# PSPS_AVNC_SRD_sensors-2020-09-19.net
KiCad netlist of a schematic drawn in EAGLE
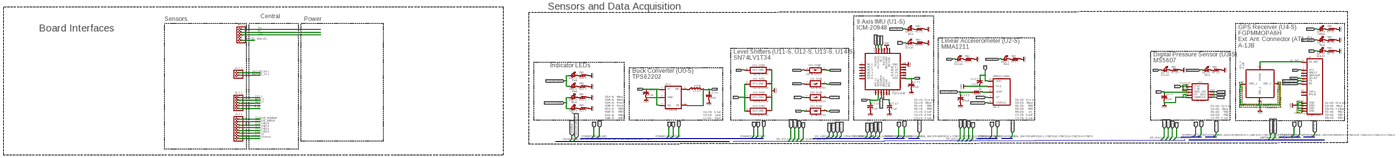
[diagram p0: schematic, sheet 1, overview]
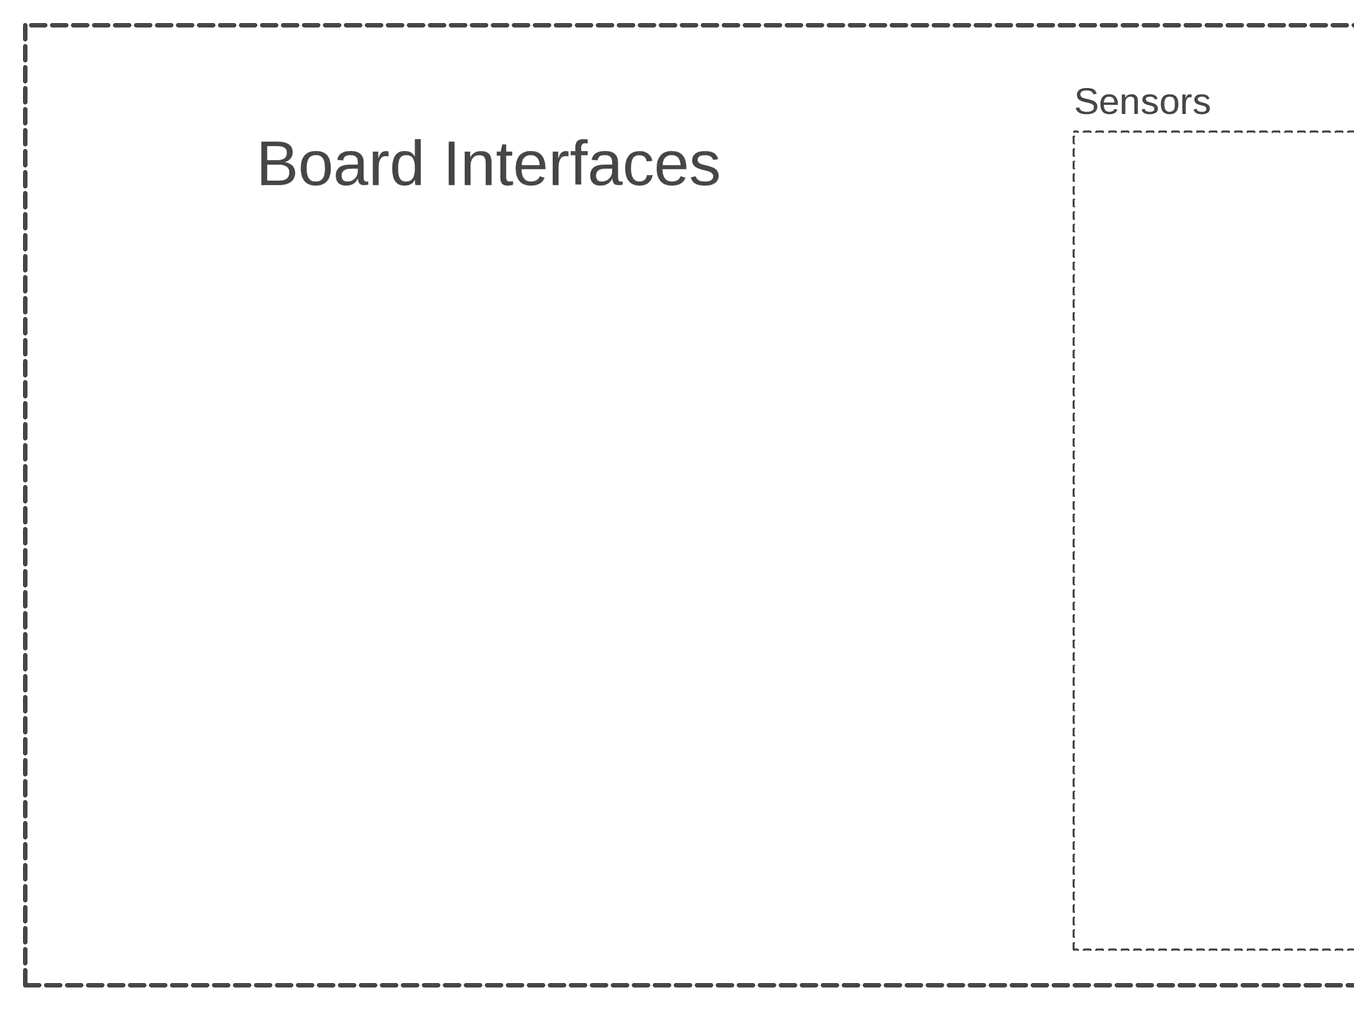
[diagram p1: schematic, sheet 1, part 1 of 4]
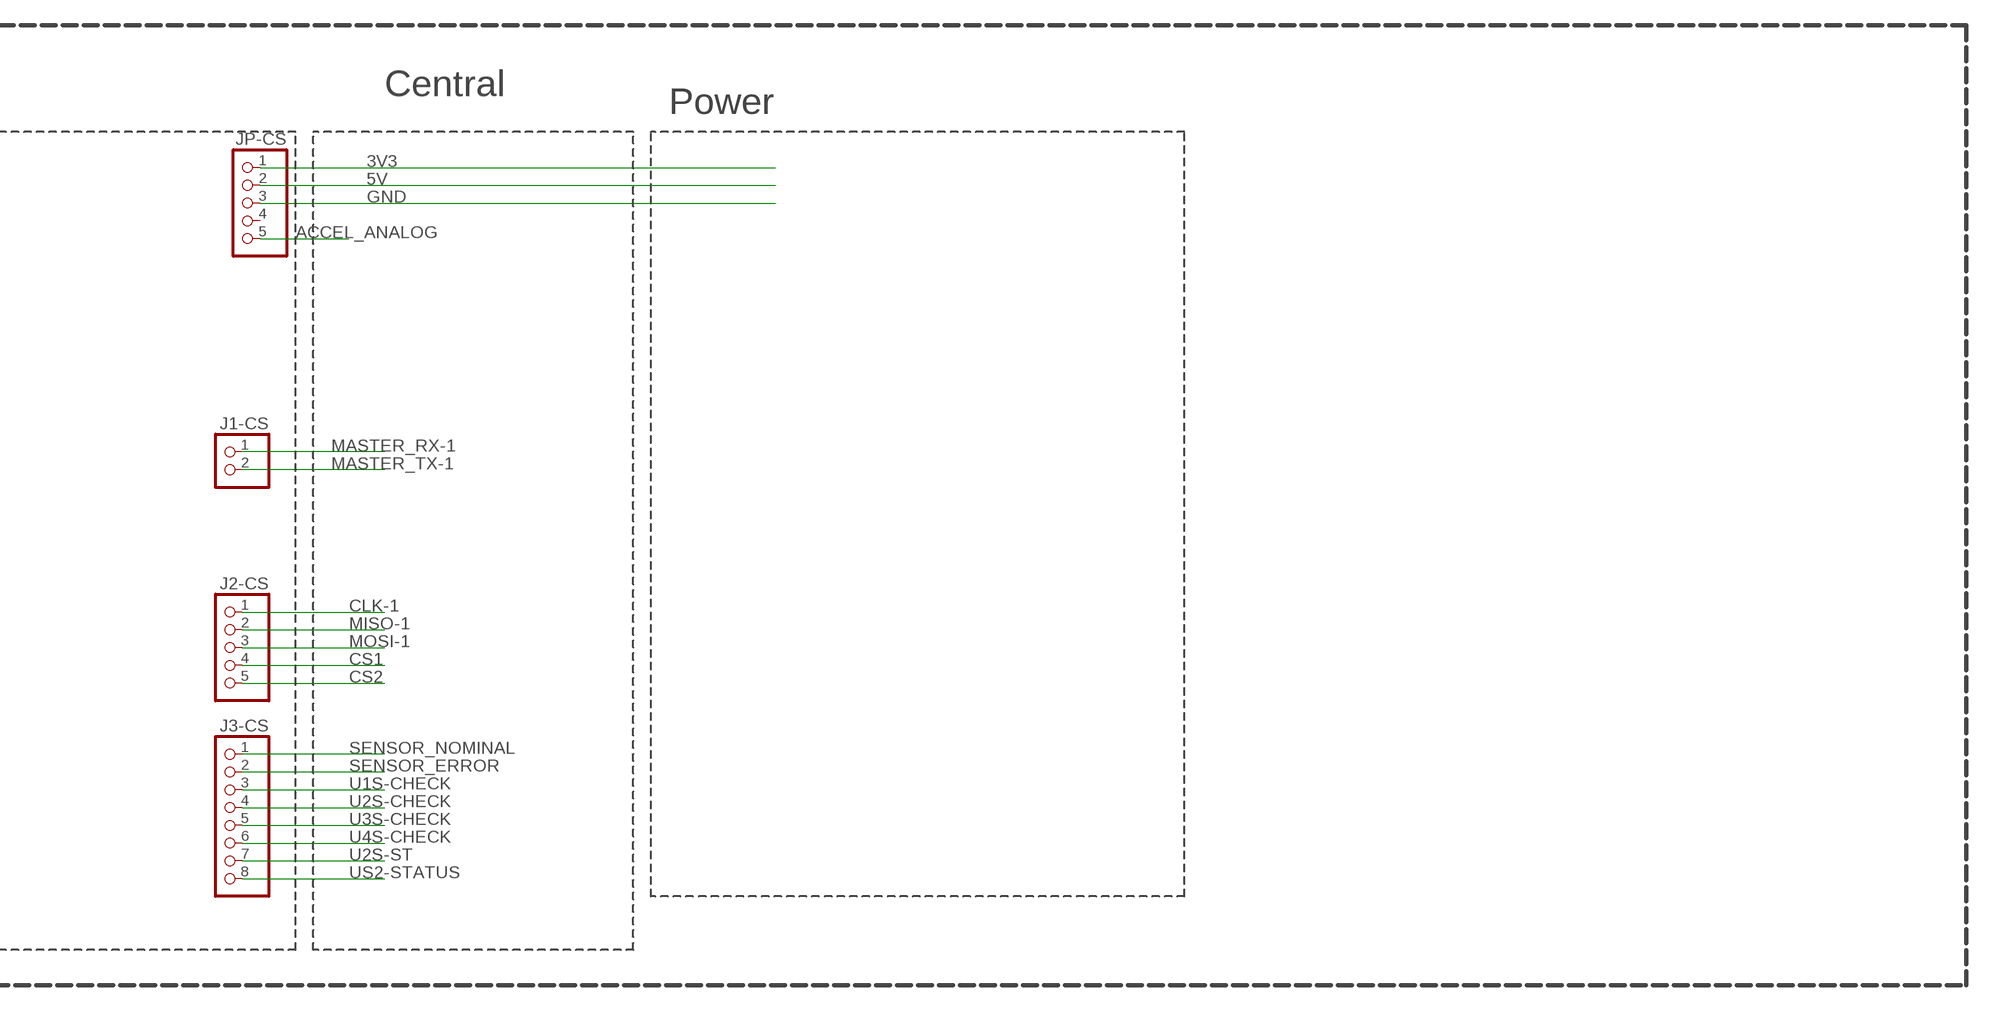
[diagram p2: schematic, sheet 1, part 2 of 4]
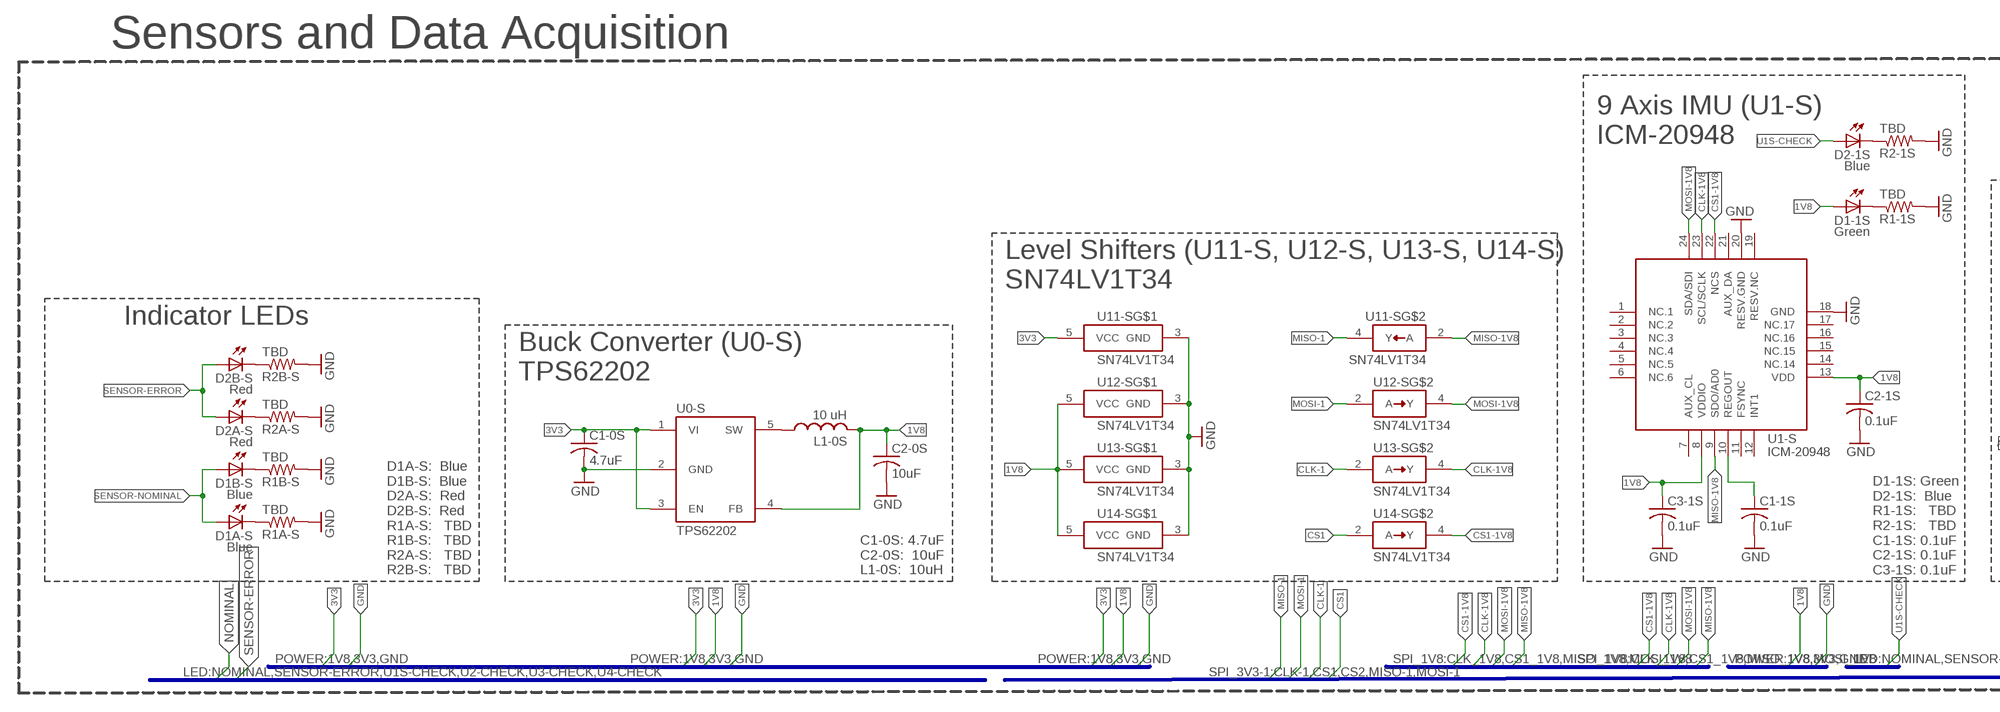
[diagram p3: schematic, sheet 1, part 3 of 4]
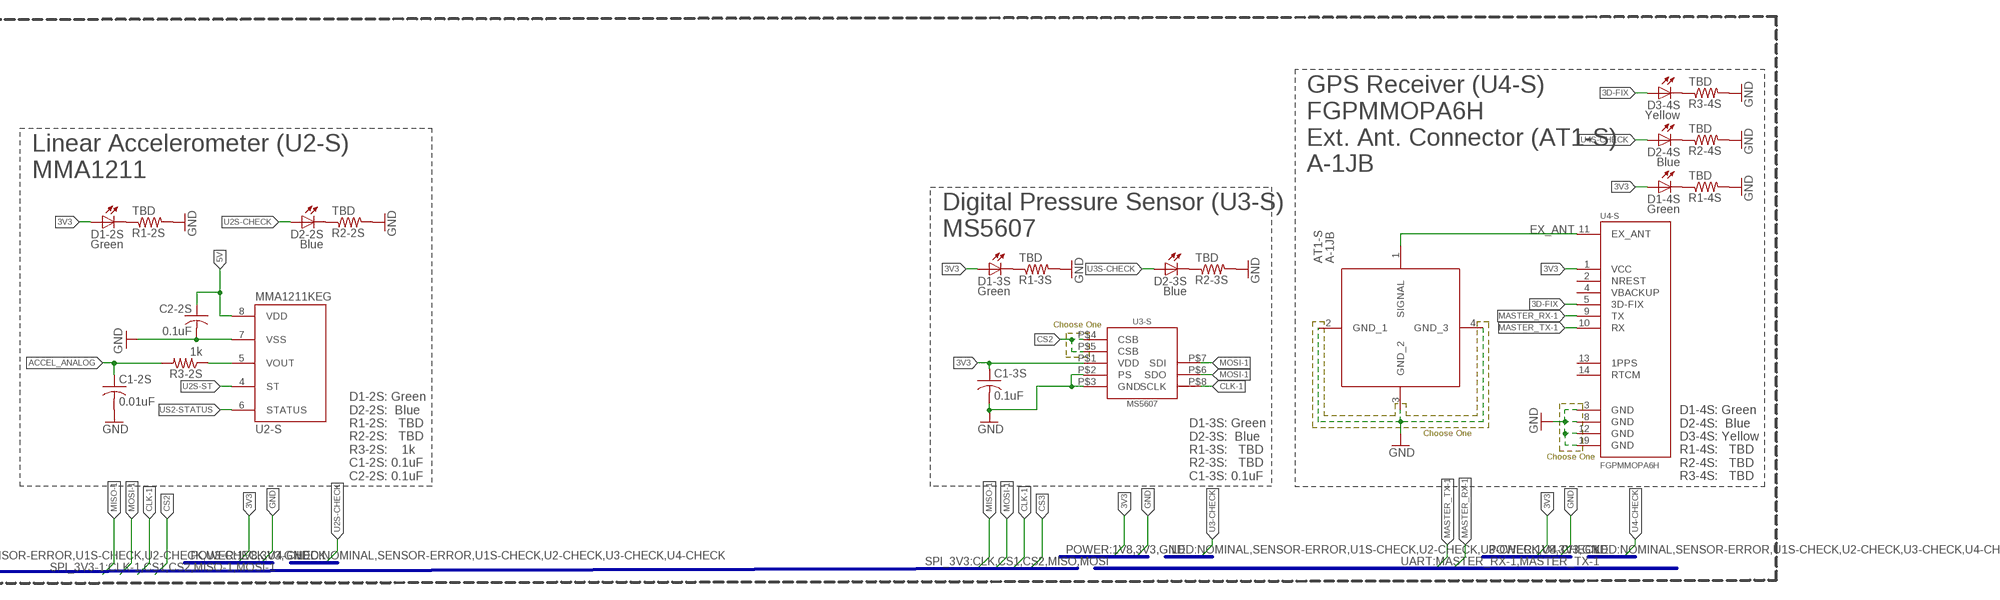
[diagram p4: schematic, sheet 1, part 4 of 4]

(export (version "E")
  (design (tool "Eeschema 10.0.6"))
  (components
    (comp (ref "AT1-S")
      (value "A-1JB")
      (footprint "eagle-import:A1JB")
      (fields (field (name "MOUSER_PART_NUMBER") "523-A-1JB"))
      (libsource (lib "eagle-import") (part "A-1JB"))
    )
    (comp (ref "C1-0S")
      (value "4.7uF")
      (footprint "eagle-import:C0805")
      (libsource (lib "eagle-import") (part "C-USC0805"))
    )
    (comp (ref "C1-1S")
      (value "0.1uF")
      (footprint "eagle-import:C0805")
      (libsource (lib "eagle-import") (part "C-USC0805"))
    )
    (comp (ref "C1-2S")
      (value "0.01uF")
      (footprint "eagle-import:C0805")
      (libsource (lib "eagle-import") (part "C-USC0805"))
    )
    (comp (ref "C1-3S")
      (value "0.1uF")
      (footprint "eagle-import:C0805")
      (libsource (lib "eagle-import") (part "C-USC0805"))
    )
    (comp (ref "C2-0S")
      (value "10uF")
      (footprint "eagle-import:C0805")
      (libsource (lib "eagle-import") (part "C-USC0805"))
    )
    (comp (ref "C2-1S")
      (value "0.1uF")
      (footprint "eagle-import:C0805")
      (libsource (lib "eagle-import") (part "C-USC0805"))
    )
    (comp (ref "C2-2S")
      (value "0.1uF")
      (footprint "eagle-import:C0805")
      (libsource (lib "eagle-import") (part "C-USC0805"))
    )
    (comp (ref "C3-1S")
      (value "0.1uF")
      (footprint "eagle-import:C0805")
      (libsource (lib "eagle-import") (part "C-USC0805"))
    )
    (comp (ref "D1-1S")
      (value "Green")
      (footprint "eagle-import:CHIPLED_0805")
      (libsource (lib "eagle-import") (part "LEDCHIPLED_0805"))
    )
    (comp (ref "D1-2S")
      (value "Green")
      (footprint "eagle-import:CHIPLED_0805")
      (libsource (lib "eagle-import") (part "LEDCHIPLED_0805"))
    )
    (comp (ref "D1-3S")
      (value "Green")
      (footprint "eagle-import:CHIPLED_0805")
      (libsource (lib "eagle-import") (part "LEDCHIPLED_0805"))
    )
    (comp (ref "D1-4S")
      (value "Green")
      (footprint "eagle-import:CHIPLED_0805")
      (libsource (lib "eagle-import") (part "LEDCHIPLED_0805"))
    )
    (comp (ref "D1A-S")
      (value "Blue")
      (footprint "eagle-import:CHIPLED_0805")
      (libsource (lib "eagle-import") (part "LEDCHIPLED_0805"))
    )
    (comp (ref "D1B-S")
      (value "Blue")
      (footprint "eagle-import:CHIPLED_0805")
      (libsource (lib "eagle-import") (part "LEDCHIPLED_0805"))
    )
    (comp (ref "D2-1S")
      (value "Blue")
      (footprint "eagle-import:CHIPLED_0805")
      (libsource (lib "eagle-import") (part "LEDCHIPLED_0805"))
    )
    (comp (ref "D2-2S")
      (value "Blue")
      (footprint "eagle-import:CHIPLED_0805")
      (libsource (lib "eagle-import") (part "LEDCHIPLED_0805"))
    )
    (comp (ref "D2-3S")
      (value "Blue")
      (footprint "eagle-import:CHIPLED_0805")
      (libsource (lib "eagle-import") (part "LEDCHIPLED_0805"))
    )
    (comp (ref "D2-4S")
      (value "Blue")
      (footprint "eagle-import:CHIPLED_0805")
      (libsource (lib "eagle-import") (part "LEDCHIPLED_0805"))
    )
    (comp (ref "D2A-S")
      (value "Red")
      (footprint "eagle-import:CHIPLED_0805")
      (libsource (lib "eagle-import") (part "LEDCHIPLED_0805"))
    )
    (comp (ref "D2B-S")
      (value "Red")
      (footprint "eagle-import:CHIPLED_0805")
      (libsource (lib "eagle-import") (part "LEDCHIPLED_0805"))
    )
    (comp (ref "D3-4S")
      (value "Yellow")
      (footprint "eagle-import:CHIPLED_0805")
      (libsource (lib "eagle-import") (part "LEDCHIPLED_0805"))
    )
    (comp (ref "J1-CS")
      (value "PINHD-1X2")
      (footprint "eagle-import:1X02")
      (libsource (lib "eagle-import") (part "PINHD-1X2"))
    )
    (comp (ref "J2-CS")
      (value "PINHD-1X5")
      (footprint "eagle-import:1X05")
      (libsource (lib "eagle-import") (part "PINHD-1X5"))
    )
    (comp (ref "J3-CS")
      (value "PINHD-1X8")
      (footprint "eagle-import:1X08")
      (libsource (lib "eagle-import") (part "PINHD-1X8"))
    )
    (comp (ref "JP-CS")
      (value "PINHD-1X5")
      (footprint "eagle-import:1X05")
      (libsource (lib "eagle-import") (part "PINHD-1X5"))
    )
    (comp (ref "L1-0S")
      (value "10 uH")
      (footprint "eagle-import:PF0560NL")
      (libsource (lib "eagle-import") (part "PF0560.103NLT"))
    )
    (comp (ref "R1-1S")
      (value "TBD")
      (footprint "eagle-import:R0805")
      (libsource (lib "eagle-import") (part "R-US_R0805"))
    )
    (comp (ref "R1-2S")
      (value "TBD")
      (footprint "eagle-import:R0805")
      (libsource (lib "eagle-import") (part "R-US_R0805"))
    )
    (comp (ref "R1-3S")
      (value "TBD")
      (footprint "eagle-import:R0805")
      (libsource (lib "eagle-import") (part "R-US_R0805"))
    )
    (comp (ref "R1-4S")
      (value "TBD")
      (footprint "eagle-import:R0805")
      (libsource (lib "eagle-import") (part "R-US_R0805"))
    )
    (comp (ref "R1A-S")
      (value "TBD")
      (footprint "eagle-import:R0805")
      (libsource (lib "eagle-import") (part "R-US_R0805"))
    )
    (comp (ref "R1B-S")
      (value "TBD")
      (footprint "eagle-import:R0805")
      (libsource (lib "eagle-import") (part "R-US_R0805"))
    )
    (comp (ref "R2-1S")
      (value "TBD")
      (footprint "eagle-import:R0805")
      (libsource (lib "eagle-import") (part "R-US_R0805"))
    )
    (comp (ref "R2-2S")
      (value "TBD")
      (footprint "eagle-import:R0805")
      (libsource (lib "eagle-import") (part "R-US_R0805"))
    )
    (comp (ref "R2-3S")
      (value "TBD")
      (footprint "eagle-import:R0805")
      (libsource (lib "eagle-import") (part "R-US_R0805"))
    )
    (comp (ref "R2-4S")
      (value "TBD")
      (footprint "eagle-import:R0805")
      (libsource (lib "eagle-import") (part "R-US_R0805"))
    )
    (comp (ref "R2A-S")
      (value "TBD")
      (footprint "eagle-import:R0805")
      (libsource (lib "eagle-import") (part "R-US_R0805"))
    )
    (comp (ref "R2B-S")
      (value "TBD")
      (footprint "eagle-import:R0805")
      (libsource (lib "eagle-import") (part "R-US_R0805"))
    )
    (comp (ref "R3-2S")
      (value "1k")
      (footprint "eagle-import:R0805")
      (libsource (lib "eagle-import") (part "R-US_R0805"))
    )
    (comp (ref "R3-4S")
      (value "TBD")
      (footprint "eagle-import:R0805")
      (libsource (lib "eagle-import") (part "R-US_R0805"))
    )
    (comp (ref "U0-S")
      (value "TPS62202")
      (footprint "eagle-import:SOT95P280X145-5")
      (libsource (lib "eagle-import") (part "TPS62202"))
    )
    (comp (ref "U1-S")
      (value "ICM-20948")
      (footprint "eagle-import:QFN40P300X300X105-25T159X175")
      (libsource (lib "eagle-import") (part "ICM-20948"))
    )
    (comp (ref "U2-S")
      (value "MMA1211KEG")
      (footprint "eagle-import:SOIC127P1041X355-16N")
      (libsource (lib "eagle-import") (part "MMA1211KEG"))
    )
    (comp (ref "U3-S")
      (value "MS5607")
      (footprint "eagle-import:MS5607")
      (libsource (lib "eagle-import") (part "MS5607"))
    )
    (comp (ref "U4-S")
      (value "FGPMMOPA6H")
      (footprint "eagle-import:SOIC127P1800X470-20N")
      (libsource (lib "eagle-import") (part "FGPMMOPA6H"))
    )
    (comp (ref "U11-S")
      (value "SN74LV1T34")
      (footprint "eagle-import:SOT65P210X110-5")
      (libsource (lib "eagle-import") (part "SN74LV1T34"))
    )
    (comp (ref "U12-S")
      (value "SN74LV1T34")
      (footprint "eagle-import:SOT65P210X110-5")
      (libsource (lib "eagle-import") (part "SN74LV1T34"))
    )
    (comp (ref "U13-S")
      (value "SN74LV1T34")
      (footprint "eagle-import:SOT65P210X110-5")
      (libsource (lib "eagle-import") (part "SN74LV1T34"))
    )
    (comp (ref "U14-S")
      (value "SN74LV1T34")
      (footprint "eagle-import:SOT65P210X110-5")
      (libsource (lib "eagle-import") (part "SN74LV1T34"))
    )
  )
  (nets
    (net (code "13") (name "/EX_ANT") (class "Default")
      (node (ref "AT1-S") (pin "1") (pinfunction "SIGNAL_1") (pintype "bidirectional"))
      (node (ref "U4-S") (pin "11") (pinfunction "EX_ANT_11") (pintype "bidirectional"))
    )
    (net (code "14") (name "/SENSOR_ERROR") (class "Default")
      (node (ref "J3-CS") (pin "2") (pinfunction "2_2") (pintype "passive"))
    )
    (net (code "15") (name "/SENSOR_NOMINAL") (class "Default")
      (node (ref "J3-CS") (pin "1") (pinfunction "1_1") (pintype "passive"))
    )
    (net (code "22") (name "1V8") (class "Default")
      (node (ref "C2-0S") (pin "1") (pinfunction "1_1") (pintype "passive"))
      (node (ref "C2-1S") (pin "1") (pinfunction "1_1") (pintype "passive"))
      (node (ref "C3-1S") (pin "1") (pinfunction "1_1") (pintype "passive"))
      (node (ref "D1-1S") (pin "A") (pinfunction "A_A") (pintype "passive"))
      (node (ref "L1-0S") (pin "P$2") (pinfunction "2_P$2") (pintype "passive"))
      (node (ref "U0-S") (pin "4") (pinfunction "FB_4") (pintype "bidirectional"))
      (node (ref "U1-S") (pin "13") (pinfunction "VDD_13") (pintype "bidirectional"))
      (node (ref "U1-S") (pin "8") (pinfunction "VDDIO_8") (pintype "bidirectional"))
      (node (ref "U12-S") (pin "5") (pinfunction "VCC_5") (pintype "bidirectional"))
      (node (ref "U13-S") (pin "5") (pinfunction "VCC_5") (pintype "bidirectional"))
      (node (ref "U14-S") (pin "5") (pinfunction "VCC_5") (pintype "bidirectional"))
    )
    (net (code "23") (name "3D-FIX") (class "Default")
      (node (ref "D3-4S") (pin "A") (pinfunction "A_A") (pintype "passive"))
      (node (ref "U4-S") (pin "5") (pinfunction "3D-FIX_5") (pintype "bidirectional"))
    )
    (net (code "24") (name "3V3") (class "Default")
      (node (ref "C1-0S") (pin "1") (pinfunction "1_1") (pintype "passive"))
      (node (ref "C1-3S") (pin "1") (pinfunction "1_1") (pintype "passive"))
      (node (ref "D1-2S") (pin "A") (pinfunction "A_A") (pintype "passive"))
      (node (ref "D1-3S") (pin "A") (pinfunction "A_A") (pintype "passive"))
      (node (ref "D1-4S") (pin "A") (pinfunction "A_A") (pintype "passive"))
      (node (ref "JP-CS") (pin "1") (pinfunction "1_1") (pintype "passive"))
      (node (ref "U0-S") (pin "1") (pinfunction "VI_1") (pintype "bidirectional"))
      (node (ref "U0-S") (pin "3") (pinfunction "EN_3") (pintype "bidirectional"))
      (node (ref "U11-S") (pin "5") (pinfunction "VCC_5") (pintype "bidirectional"))
      (node (ref "U3-S") (pin "P$1") (pinfunction "VDD_P$1") (pintype "bidirectional"))
      (node (ref "U4-S") (pin "1") (pinfunction "VCC_1") (pintype "bidirectional"))
    )
    (net (code "25") (name "5V") (class "Default")
      (node (ref "C2-2S") (pin "1") (pinfunction "1_1") (pintype "passive"))
      (node (ref "JP-CS") (pin "2") (pinfunction "2_2") (pintype "passive"))
      (node (ref "U2-S") (pin "8") (pinfunction "VDD_8") (pintype "bidirectional"))
    )
    (net (code "26") (name "ACCEL_ANALOG") (class "Default")
      (node (ref "C1-2S") (pin "1") (pinfunction "1_1") (pintype "passive"))
      (node (ref "JP-CS") (pin "5") (pinfunction "5_5") (pintype "passive"))
      (node (ref "R3-2S") (pin "2") (pinfunction "2_2") (pintype "passive"))
    )
    (net (code "27") (name "CLK-1") (class "Default")
      (node (ref "J2-CS") (pin "1") (pinfunction "1_1") (pintype "passive"))
      (node (ref "U13-S") (pin "2") (pinfunction "A_2") (pintype "bidirectional"))
      (node (ref "U3-S") (pin "P$8") (pinfunction "SCLK_P$8") (pintype "bidirectional"))
    )
    (net (code "28") (name "CLK-1V8") (class "Default")
      (node (ref "U1-S") (pin "23") (pinfunction "SCL/SCLK_23") (pintype "bidirectional"))
      (node (ref "U13-S") (pin "4") (pinfunction "Y_4") (pintype "bidirectional"))
    )
    (net (code "29") (name "CS1") (class "Default")
      (node (ref "J2-CS") (pin "4") (pinfunction "4_4") (pintype "passive"))
      (node (ref "U14-S") (pin "2") (pinfunction "A_2") (pintype "bidirectional"))
    )
    (net (code "30") (name "CS1-1V8") (class "Default")
      (node (ref "U1-S") (pin "22") (pinfunction "NCS_22") (pintype "bidirectional"))
      (node (ref "U14-S") (pin "4") (pinfunction "Y_4") (pintype "bidirectional"))
    )
    (net (code "31") (name "CS2") (class "Default")
      (node (ref "J2-CS") (pin "5") (pinfunction "5_5") (pintype "passive"))
      (node (ref "U3-S") (pin "P$4") (pinfunction "CSB_P$4") (pintype "bidirectional"))
      (node (ref "U3-S") (pin "P$5") (pinfunction "CSB_P$5") (pintype "bidirectional"))
    )
    (net (code "33") (name "GND") (class "Default")
      (node (ref "AT1-S") (pin "2") (pinfunction "GND_1_2") (pintype "bidirectional"))
      (node (ref "AT1-S") (pin "3") (pinfunction "GND_2_3") (pintype "bidirectional"))
      (node (ref "AT1-S") (pin "4") (pinfunction "GND_3_4") (pintype "bidirectional"))
      (node (ref "C1-0S") (pin "2") (pinfunction "2_2") (pintype "passive"))
      (node (ref "C1-1S") (pin "2") (pinfunction "2_2") (pintype "passive"))
      (node (ref "C1-2S") (pin "2") (pinfunction "2_2") (pintype "passive"))
      (node (ref "C1-3S") (pin "2") (pinfunction "2_2") (pintype "passive"))
      (node (ref "C2-0S") (pin "2") (pinfunction "2_2") (pintype "passive"))
      (node (ref "C2-1S") (pin "2") (pinfunction "2_2") (pintype "passive"))
      (node (ref "C2-2S") (pin "2") (pinfunction "2_2") (pintype "passive"))
      (node (ref "C3-1S") (pin "2") (pinfunction "2_2") (pintype "passive"))
      (node (ref "JP-CS") (pin "3") (pinfunction "3_3") (pintype "passive"))
      (node (ref "R1-1S") (pin "2") (pinfunction "2_2") (pintype "passive"))
      (node (ref "R1-2S") (pin "2") (pinfunction "2_2") (pintype "passive"))
      (node (ref "R1-3S") (pin "2") (pinfunction "2_2") (pintype "passive"))
      (node (ref "R1-4S") (pin "2") (pinfunction "2_2") (pintype "passive"))
      (node (ref "R1A-S") (pin "2") (pinfunction "2_2") (pintype "passive"))
      (node (ref "R1B-S") (pin "2") (pinfunction "2_2") (pintype "passive"))
      (node (ref "R2-1S") (pin "2") (pinfunction "2_2") (pintype "passive"))
      (node (ref "R2-2S") (pin "2") (pinfunction "2_2") (pintype "passive"))
      (node (ref "R2-3S") (pin "2") (pinfunction "2_2") (pintype "passive"))
      (node (ref "R2-4S") (pin "2") (pinfunction "2_2") (pintype "passive"))
      (node (ref "R2A-S") (pin "2") (pinfunction "2_2") (pintype "passive"))
      (node (ref "R2B-S") (pin "2") (pinfunction "2_2") (pintype "passive"))
      (node (ref "R3-4S") (pin "2") (pinfunction "2_2") (pintype "passive"))
      (node (ref "U0-S") (pin "2") (pinfunction "GND_2") (pintype "bidirectional"))
      (node (ref "U1-S") (pin "18") (pinfunction "GND_18") (pintype "bidirectional"))
      (node (ref "U1-S") (pin "20") (pinfunction "RESV.GND_20") (pintype "bidirectional"))
      (node (ref "U11-S") (pin "3") (pinfunction "GND_3") (pintype "bidirectional"))
      (node (ref "U12-S") (pin "3") (pinfunction "GND_3") (pintype "bidirectional"))
      (node (ref "U13-S") (pin "3") (pinfunction "GND_3") (pintype "bidirectional"))
      (node (ref "U14-S") (pin "3") (pinfunction "GND_3") (pintype "bidirectional"))
      (node (ref "U2-S") (pin "7") (pinfunction "VSS_7") (pintype "bidirectional"))
      (node (ref "U3-S") (pin "P$2") (pinfunction "PS_P$2") (pintype "bidirectional"))
      (node (ref "U3-S") (pin "P$3") (pinfunction "GND_P$3") (pintype "bidirectional"))
      (node (ref "U4-S") (pin "12") (pinfunction "GND_12") (pintype "bidirectional"))
      (node (ref "U4-S") (pin "19") (pinfunction "GND_19") (pintype "bidirectional"))
      (node (ref "U4-S") (pin "3") (pinfunction "GND_3") (pintype "bidirectional"))
      (node (ref "U4-S") (pin "8") (pinfunction "GND_8") (pintype "bidirectional"))
    )
    (net (code "34") (name "MASTER_RX-1") (class "Default")
      (node (ref "J1-CS") (pin "1") (pinfunction "1_1") (pintype "passive"))
      (node (ref "U4-S") (pin "9") (pinfunction "TX_9") (pintype "bidirectional"))
    )
    (net (code "35") (name "MASTER_TX-1") (class "Default")
      (node (ref "J1-CS") (pin "2") (pinfunction "2_2") (pintype "passive"))
      (node (ref "U4-S") (pin "10") (pinfunction "RX_10") (pintype "bidirectional"))
    )
    (net (code "36") (name "MISO-1") (class "Default")
      (node (ref "J2-CS") (pin "2") (pinfunction "2_2") (pintype "passive"))
      (node (ref "U11-S") (pin "4") (pinfunction "Y_4") (pintype "bidirectional"))
    )
    (net (code "37") (name "MISO-1V8") (class "Default")
      (node (ref "U1-S") (pin "9") (pinfunction "SDO/AD0_9") (pintype "bidirectional"))
      (node (ref "U11-S") (pin "2") (pinfunction "A_2") (pintype "bidirectional"))
    )
    (net (code "38") (name "MOSI-1") (class "Default")
      (node (ref "J2-CS") (pin "3") (pinfunction "3_3") (pintype "passive"))
      (node (ref "U12-S") (pin "2") (pinfunction "A_2") (pintype "bidirectional"))
      (node (ref "U3-S") (pin "P$6") (pinfunction "SDO_P$6") (pintype "bidirectional"))
      (node (ref "U3-S") (pin "P$7") (pinfunction "SDI_P$7") (pintype "bidirectional"))
    )
    (net (code "39") (name "MOSI-1V8") (class "Default")
      (node (ref "U1-S") (pin "24") (pinfunction "SDA/SDI_24") (pintype "bidirectional"))
      (node (ref "U12-S") (pin "4") (pinfunction "Y_4") (pintype "bidirectional"))
    )
    (net (code "41") (name "Net-(D1-1S-PadC)") (class "Default")
      (node (ref "D1-1S") (pin "C") (pinfunction "C_C") (pintype "passive"))
      (node (ref "R1-1S") (pin "1") (pinfunction "1_1") (pintype "passive"))
    )
    (net (code "42") (name "Net-(D1-2S-PadC)") (class "Default")
      (node (ref "D1-2S") (pin "C") (pinfunction "C_C") (pintype "passive"))
      (node (ref "R1-2S") (pin "1") (pinfunction "1_1") (pintype "passive"))
    )
    (net (code "43") (name "Net-(D1-3S-PadC)") (class "Default")
      (node (ref "D1-3S") (pin "C") (pinfunction "C_C") (pintype "passive"))
      (node (ref "R1-3S") (pin "1") (pinfunction "1_1") (pintype "passive"))
    )
    (net (code "44") (name "Net-(D1-4S-PadC)") (class "Default")
      (node (ref "D1-4S") (pin "C") (pinfunction "C_C") (pintype "passive"))
      (node (ref "R1-4S") (pin "1") (pinfunction "1_1") (pintype "passive"))
    )
    (net (code "45") (name "Net-(D1A-S-PadC)") (class "Default")
      (node (ref "D1A-S") (pin "C") (pinfunction "C_C") (pintype "passive"))
      (node (ref "R1A-S") (pin "1") (pinfunction "1_1") (pintype "passive"))
    )
    (net (code "46") (name "Net-(D1B-S-PadC)") (class "Default")
      (node (ref "D1B-S") (pin "C") (pinfunction "C_C") (pintype "passive"))
      (node (ref "R1B-S") (pin "1") (pinfunction "1_1") (pintype "passive"))
    )
    (net (code "47") (name "Net-(D2-1S-PadC)") (class "Default")
      (node (ref "D2-1S") (pin "C") (pinfunction "C_C") (pintype "passive"))
      (node (ref "R2-1S") (pin "1") (pinfunction "1_1") (pintype "passive"))
    )
    (net (code "48") (name "Net-(D2-2S-PadC)") (class "Default")
      (node (ref "D2-2S") (pin "C") (pinfunction "C_C") (pintype "passive"))
      (node (ref "R2-2S") (pin "1") (pinfunction "1_1") (pintype "passive"))
    )
    (net (code "49") (name "Net-(D2-3S-PadC)") (class "Default")
      (node (ref "D2-3S") (pin "C") (pinfunction "C_C") (pintype "passive"))
      (node (ref "R2-3S") (pin "1") (pinfunction "1_1") (pintype "passive"))
    )
    (net (code "50") (name "Net-(D2-4S-PadC)") (class "Default")
      (node (ref "D2-4S") (pin "C") (pinfunction "C_C") (pintype "passive"))
      (node (ref "R2-4S") (pin "1") (pinfunction "1_1") (pintype "passive"))
    )
    (net (code "51") (name "Net-(D2A-S-PadC)") (class "Default")
      (node (ref "D2A-S") (pin "C") (pinfunction "C_C") (pintype "passive"))
      (node (ref "R2A-S") (pin "1") (pinfunction "1_1") (pintype "passive"))
    )
    (net (code "52") (name "Net-(D2B-S-PadC)") (class "Default")
      (node (ref "D2B-S") (pin "C") (pinfunction "C_C") (pintype "passive"))
      (node (ref "R2B-S") (pin "1") (pinfunction "1_1") (pintype "passive"))
    )
    (net (code "53") (name "Net-(D3-4S-PadC)") (class "Default")
      (node (ref "D3-4S") (pin "C") (pinfunction "C_C") (pintype "passive"))
      (node (ref "R3-4S") (pin "1") (pinfunction "1_1") (pintype "passive"))
    )
    (net (code "54") (name "Net-(L1-0S-1)") (class "Default")
      (node (ref "L1-0S") (pin "P$1") (pinfunction "1_P$1") (pintype "passive"))
      (node (ref "U0-S") (pin "5") (pinfunction "SW_5") (pintype "bidirectional"))
    )
    (net (code "55") (name "Net-(U1-S-REGOUT)") (class "Default")
      (node (ref "C1-1S") (pin "1") (pinfunction "1_1") (pintype "passive"))
      (node (ref "U1-S") (pin "10") (pinfunction "REGOUT_10") (pintype "bidirectional"))
    )
    (net (code "56") (name "Net-(U2-S-VOUT)") (class "Default")
      (node (ref "R3-2S") (pin "1") (pinfunction "1_1") (pintype "passive"))
      (node (ref "U2-S") (pin "5") (pinfunction "VOUT_5") (pintype "bidirectional"))
    )
    (net (code "57") (name "SENSOR-ERROR") (class "Default")
      (node (ref "D2A-S") (pin "A") (pinfunction "A_A") (pintype "passive"))
      (node (ref "D2B-S") (pin "A") (pinfunction "A_A") (pintype "passive"))
    )
    (net (code "58") (name "SENSOR-NOMINAL") (class "Default")
      (node (ref "D1A-S") (pin "A") (pinfunction "A_A") (pintype "passive"))
      (node (ref "D1B-S") (pin "A") (pinfunction "A_A") (pintype "passive"))
    )
    (net (code "59") (name "U1S-CHECK") (class "Default")
      (node (ref "D2-1S") (pin "A") (pinfunction "A_A") (pintype "passive"))
      (node (ref "J3-CS") (pin "3") (pinfunction "3_3") (pintype "passive"))
    )
    (net (code "60") (name "U2S-CHECK") (class "Default")
      (node (ref "D2-2S") (pin "A") (pinfunction "A_A") (pintype "passive"))
      (node (ref "J3-CS") (pin "4") (pinfunction "4_4") (pintype "passive"))
    )
    (net (code "61") (name "U2S-ST") (class "Default")
      (node (ref "J3-CS") (pin "7") (pinfunction "7_7") (pintype "passive"))
      (node (ref "U2-S") (pin "4") (pinfunction "ST_4") (pintype "bidirectional"))
    )
    (net (code "63") (name "U3S-CHECK") (class "Default")
      (node (ref "D2-3S") (pin "A") (pinfunction "A_A") (pintype "passive"))
      (node (ref "J3-CS") (pin "5") (pinfunction "5_5") (pintype "passive"))
    )
    (net (code "65") (name "U4S-CHECK") (class "Default")
      (node (ref "D2-4S") (pin "A") (pinfunction "A_A") (pintype "passive"))
      (node (ref "J3-CS") (pin "6") (pinfunction "6_6") (pintype "passive"))
    )
    (net (code "66") (name "US2-STATUS") (class "Default")
      (node (ref "J3-CS") (pin "8") (pinfunction "8_8") (pintype "passive"))
      (node (ref "U2-S") (pin "6") (pinfunction "STATUS_6") (pintype "bidirectional"))
    )
    (net (code "67") (name "unconnected-(JP-CS-Pad4)") (class "Default")
      (node (ref "JP-CS") (pin "4") (pinfunction "4_4") (pintype "passive"))
    )
    (net (code "68") (name "unconnected-(U1-S-AUX_CL-Pad7)") (class "Default")
      (node (ref "U1-S") (pin "7") (pinfunction "AUX_CL_7") (pintype "bidirectional"))
    )
    (net (code "69") (name "unconnected-(U1-S-AUX_DA-Pad21)") (class "Default")
      (node (ref "U1-S") (pin "21") (pinfunction "AUX_DA_21") (pintype "bidirectional"))
    )
    (net (code "70") (name "unconnected-(U1-S-FSYNC-Pad11)") (class "Default")
      (node (ref "U1-S") (pin "11") (pinfunction "FSYNC_11") (pintype "bidirectional"))
    )
    (net (code "71") (name "unconnected-(U1-S-INT1-Pad12)") (class "Default")
      (node (ref "U1-S") (pin "12") (pinfunction "INT1_12") (pintype "bidirectional"))
    )
    (net (code "72") (name "unconnected-(U1-S-NC.1-Pad1)") (class "Default")
      (node (ref "U1-S") (pin "1") (pinfunction "NC.1_1") (pintype "bidirectional"))
    )
    (net (code "73") (name "unconnected-(U1-S-NC.2-Pad2)") (class "Default")
      (node (ref "U1-S") (pin "2") (pinfunction "NC.2_2") (pintype "bidirectional"))
    )
    (net (code "74") (name "unconnected-(U1-S-NC.3-Pad3)") (class "Default")
      (node (ref "U1-S") (pin "3") (pinfunction "NC.3_3") (pintype "bidirectional"))
    )
    (net (code "75") (name "unconnected-(U1-S-NC.4-Pad4)") (class "Default")
      (node (ref "U1-S") (pin "4") (pinfunction "NC.4_4") (pintype "bidirectional"))
    )
    (net (code "76") (name "unconnected-(U1-S-NC.5-Pad5)") (class "Default")
      (node (ref "U1-S") (pin "5") (pinfunction "NC.5_5") (pintype "bidirectional"))
    )
    (net (code "77") (name "unconnected-(U1-S-NC.6-Pad6)") (class "Default")
      (node (ref "U1-S") (pin "6") (pinfunction "NC.6_6") (pintype "bidirectional"))
    )
    (net (code "78") (name "unconnected-(U1-S-NC.14-Pad14)") (class "Default")
      (node (ref "U1-S") (pin "14") (pinfunction "NC.14_14") (pintype "bidirectional"))
    )
    (net (code "79") (name "unconnected-(U1-S-NC.15-Pad15)") (class "Default")
      (node (ref "U1-S") (pin "15") (pinfunction "NC.15_15") (pintype "bidirectional"))
    )
    (net (code "80") (name "unconnected-(U1-S-NC.16-Pad16)") (class "Default")
      (node (ref "U1-S") (pin "16") (pinfunction "NC.16_16") (pintype "bidirectional"))
    )
    (net (code "81") (name "unconnected-(U1-S-NC.17-Pad17)") (class "Default")
      (node (ref "U1-S") (pin "17") (pinfunction "NC.17_17") (pintype "bidirectional"))
    )
    (net (code "82") (name "unconnected-(U1-S-RESV.NC-Pad19)") (class "Default")
      (node (ref "U1-S") (pin "19") (pinfunction "RESV.NC_19") (pintype "bidirectional"))
    )
    (net (code "83") (name "unconnected-(U4-S-1PPS-Pad13)") (class "Default")
      (node (ref "U4-S") (pin "13") (pinfunction "1PPS_13") (pintype "bidirectional"))
    )
    (net (code "84") (name "unconnected-(U4-S-NREST-Pad2)") (class "Default")
      (node (ref "U4-S") (pin "2") (pinfunction "NREST_2") (pintype "bidirectional"))
    )
    (net (code "85") (name "unconnected-(U4-S-RTCM-Pad14)") (class "Default")
      (node (ref "U4-S") (pin "14") (pinfunction "RTCM_14") (pintype "bidirectional"))
    )
    (net (code "86") (name "unconnected-(U4-S-VBACKUP-Pad4)") (class "Default")
      (node (ref "U4-S") (pin "4") (pinfunction "VBACKUP_4") (pintype "bidirectional"))
    )
  )
)
